# main.net
KiCad netlist of a schematic drawn in Altium Designer
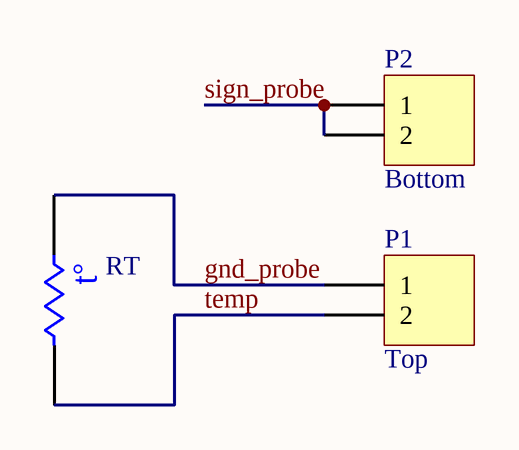
[diagram p0: main.SchDoc]

(export (version "E")
  (design (tool "Eeschema 10.0.6"))
  (components
    (comp (ref "P1")
      (value "Top")
      (footprint "Connectors:header2")
      (description "Header, 2-Pin")
      (fields (field (name "PUBLISHER") "Altium Limited"))
      (libsource (lib "Miscellaneous Connectors") (part "Header 2"))
    )
    (comp (ref "P2")
      (value "Bottom")
      (footprint "Connectors:header2")
      (description "Header, 2-Pin")
      (fields (field (name "PUBLISHER") "Altium Limited"))
      (libsource (lib "Miscellaneous Connectors") (part "Header 2"))
    )
    (comp (ref "RT")
      (value "Res Thermal")
      (footprint "6-0805_M")
      (description "Thermistor")
      (fields (field (name "PUBLISHER") "Altium Limited"))
      (libsource (lib "Miscellaneous Devices") (part "Res Thermal"))
    )
  )
  (nets
    (net (code "1") (name "/gnd_probe") (class "Default")
      (node (ref "P1") (pin "1") (pinfunction "1_1") (pintype "passive"))
      (node (ref "RT") (pin "1") (pinfunction "1_1") (pintype "passive"))
    )
    (net (code "2") (name "/sign_probe") (class "Default")
      (node (ref "P2") (pin "1") (pinfunction "1_1") (pintype "passive"))
      (node (ref "P2") (pin "2") (pinfunction "2_2") (pintype "passive"))
    )
    (net (code "3") (name "/temp") (class "Default")
      (node (ref "P1") (pin "2") (pinfunction "2_2") (pintype "passive"))
      (node (ref "RT") (pin "2") (pinfunction "2_2") (pintype "passive"))
    )
  )
)
